# Digital_Connectors_and_IHM.net
KiCad netlist of a schematic drawn in Altium Designer
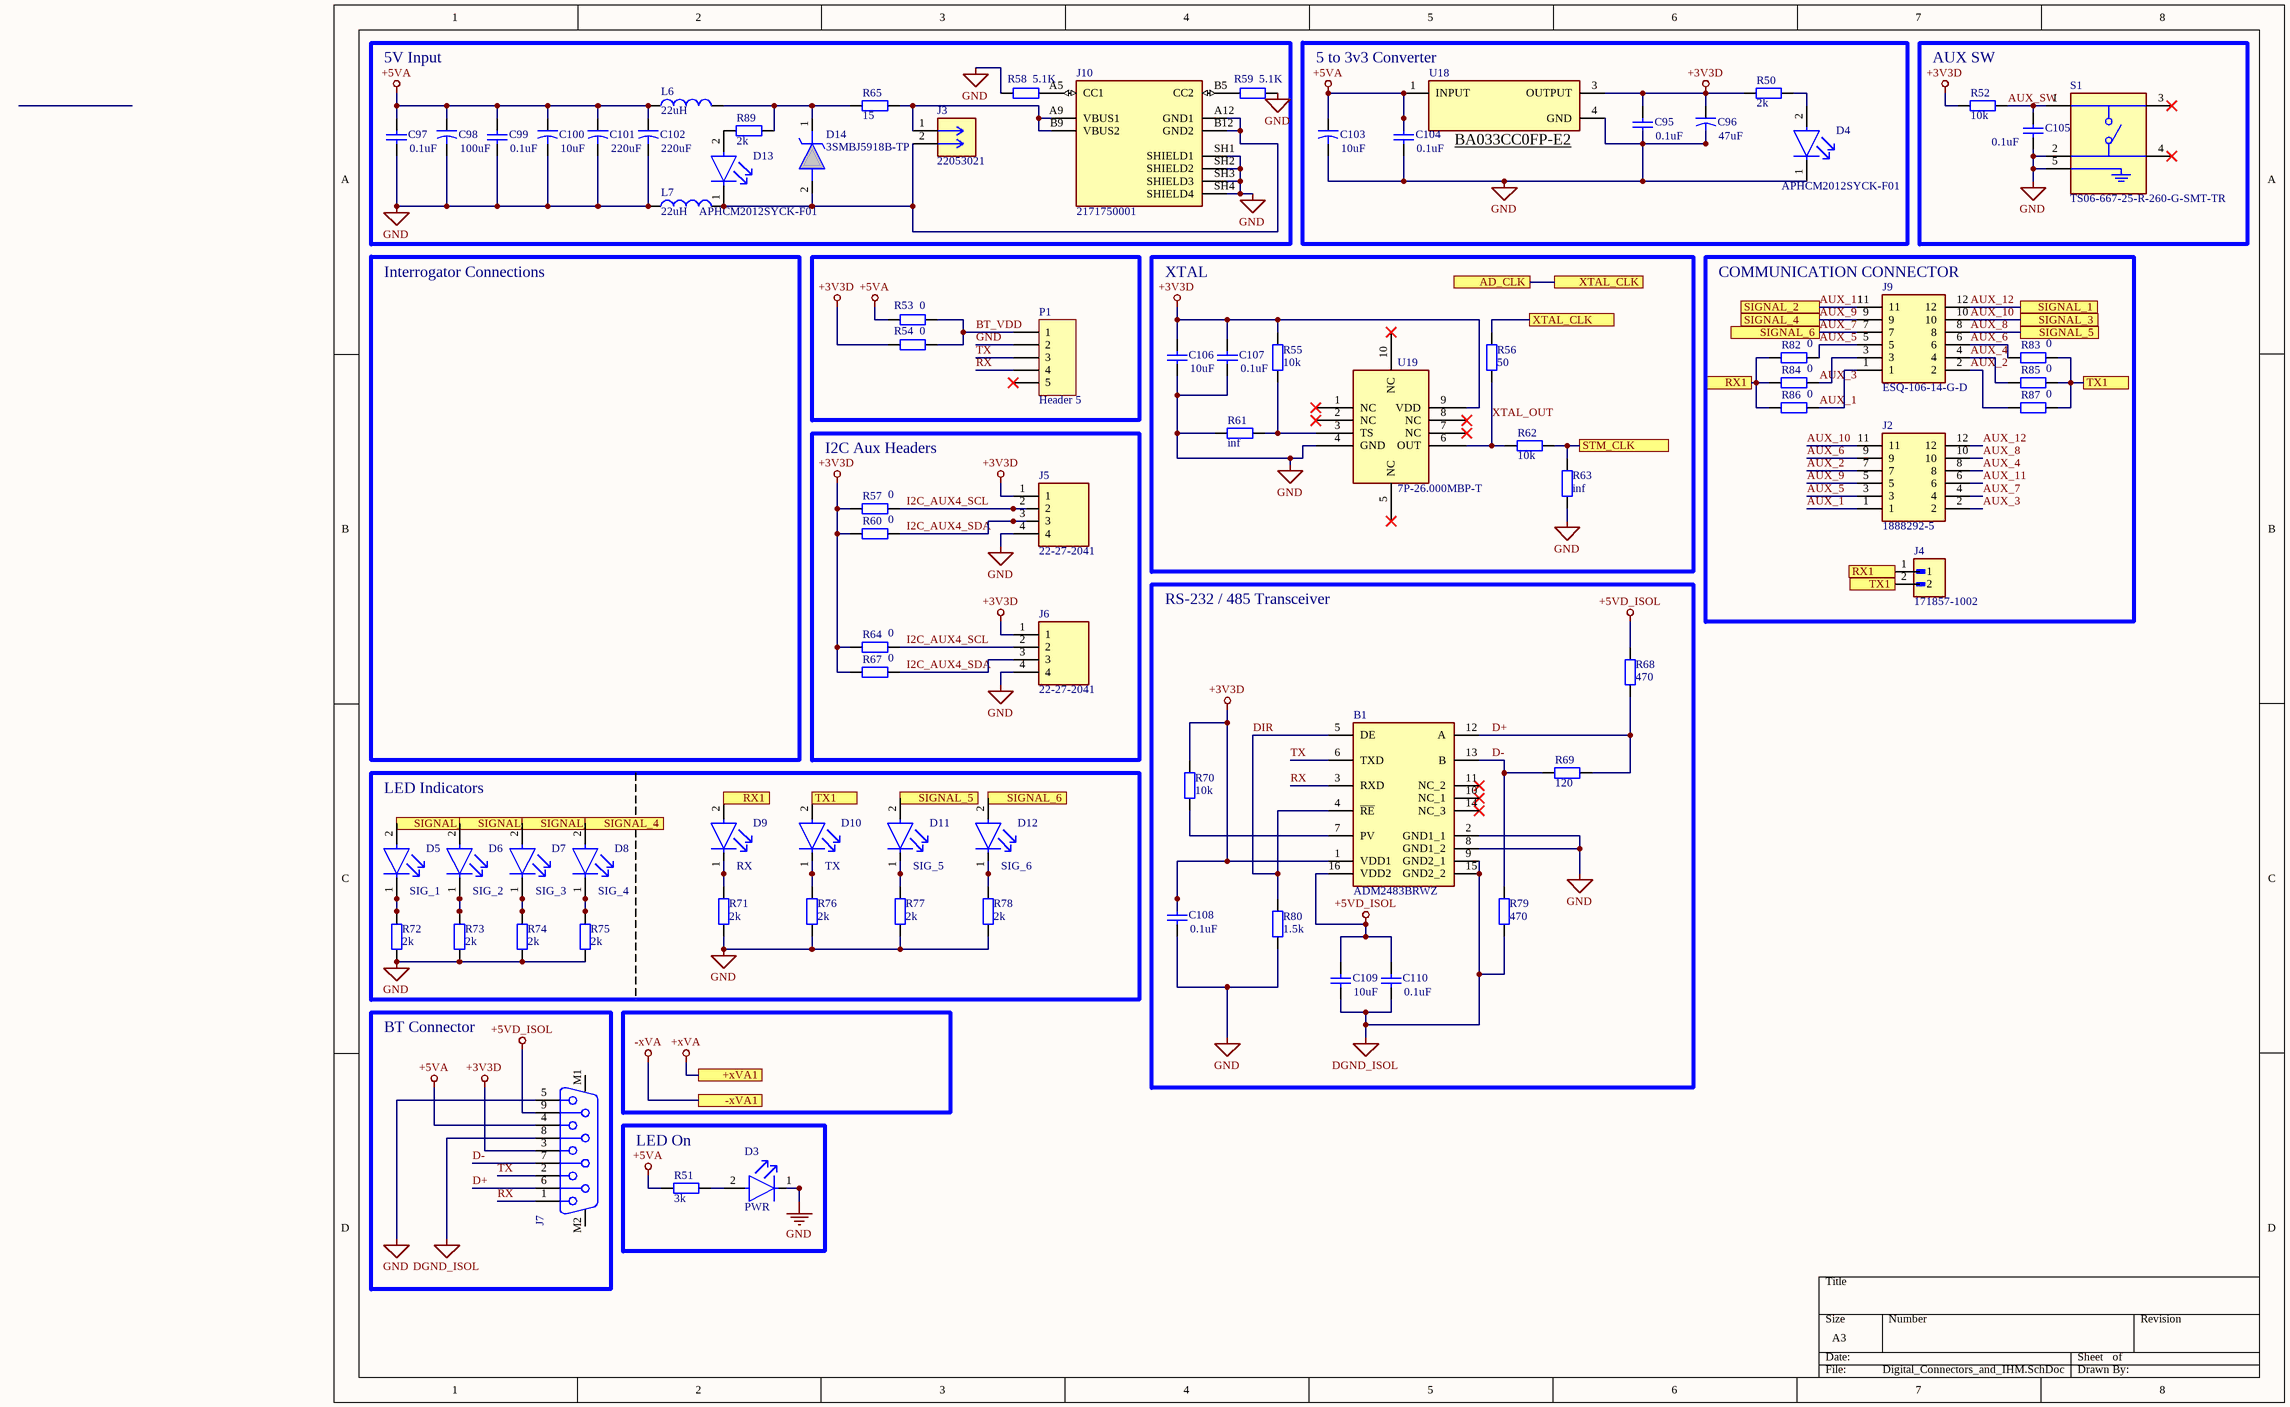
[diagram p0: Digital_Connectors_and_IHM.SchDoc]

(export (version "E")
  (design (tool "Eeschema 10.0.6"))
  (components
    (comp (ref "B1")
      (value "ADM2483BRWZ")
      (footprint "ADM2483BRWZ")
      (description "Half-Duplex, iCoupler Isolated RS-485 Transceiver")
      (fields (field (name "MOUSER PART NUMBER") "584-ADM2483BRWZ"))
      (libsource (lib "Lib_Schematic_Gyro_Single_Axis") (part "ADM2483BRWZ"))
    )
    (comp (ref "C95")
      (value "0.1uF")
      (footprint "CC_0805")
      (description "Capacitor")
      (fields (field (name "Comment") "Cap") (field (name "PUBLISHER") "Altium Limited"))
      (libsource (lib "Miscellaneous Devices") (part "Cap"))
    )
    (comp (ref "C96")
      (value "47uF")
      (footprint "CC_0805")
      (description "Capacitor")
      (fields (field (name "Comment") "Cap2") (field (name "PUBLISHER") "Altium Limited"))
      (libsource (lib "Miscellaneous Devices") (part "Cap2"))
    )
    (comp (ref "C97")
      (value "0.1uF")
      (footprint "CC_0805")
      (description "Capacitor")
      (fields (field (name "Comment") "Cap") (field (name "PUBLISHER") "Altium Limited"))
      (libsource (lib "Miscellaneous Devices") (part "Cap"))
    )
    (comp (ref "C98")
      (value "100uF")
      (footprint "CC_0805")
      (description "Capacitor")
      (fields (field (name "Comment") "Cap2") (field (name "PUBLISHER") "Altium Limited"))
      (libsource (lib "Miscellaneous Devices") (part "Cap2"))
    )
    (comp (ref "C99")
      (value "0.1uF")
      (footprint "CC_0805")
      (description "Capacitor")
      (fields (field (name "Comment") "Cap") (field (name "PUBLISHER") "Altium Limited"))
      (libsource (lib "Miscellaneous Devices") (part "Cap"))
    )
    (comp (ref "C100")
      (value "10uF")
      (footprint "CC_0805")
      (description "Capacitor")
      (fields (field (name "Comment") "Cap2") (field (name "PUBLISHER") "Altium Limited"))
      (libsource (lib "Miscellaneous Devices") (part "Cap2"))
    )
    (comp (ref "C101")
      (value "220uF")
      (footprint "CC_0805")
      (description "Capacitor")
      (fields (field (name "Comment") "Cap2") (field (name "PUBLISHER") "Altium Limited"))
      (libsource (lib "Miscellaneous Devices") (part "Cap2"))
    )
    (comp (ref "C102")
      (value "220uF")
      (footprint "CC_0805")
      (description "Capacitor")
      (fields (field (name "Comment") "Cap2") (field (name "PUBLISHER") "Altium Limited"))
      (libsource (lib "Miscellaneous Devices") (part "Cap2"))
    )
    (comp (ref "C103")
      (value "10uF")
      (footprint "CC_0805")
      (description "Capacitor")
      (fields (field (name "Comment") "Cap2") (field (name "PUBLISHER") "Altium Limited"))
      (libsource (lib "Miscellaneous Devices") (part "Cap2"))
    )
    (comp (ref "C104")
      (value "0.1uF")
      (footprint "CC_0805")
      (description "Capacitor")
      (fields (field (name "Comment") "Cap") (field (name "PUBLISHER") "Altium Limited"))
      (libsource (lib "Miscellaneous Devices") (part "Cap"))
    )
    (comp (ref "C105")
      (value "0.1uF")
      (footprint "CC_0805")
      (description "Capacitor")
      (fields (field (name "Comment") "Cap") (field (name "PUBLISHER") "Altium Limited"))
      (libsource (lib "Miscellaneous Devices") (part "Cap"))
    )
    (comp (ref "C106")
      (value "10uF")
      (footprint "CC_0805")
      (description "Capacitor")
      (fields (field (name "Comment") "Cap") (field (name "PUBLISHER") "Altium Limited"))
      (libsource (lib "Miscellaneous Devices") (part "Cap"))
    )
    (comp (ref "C107")
      (value "0.1uF")
      (footprint "CC_0805")
      (description "Capacitor")
      (fields (field (name "Comment") "Cap") (field (name "PUBLISHER") "Altium Limited"))
      (libsource (lib "Miscellaneous Devices") (part "Cap"))
    )
    (comp (ref "C108")
      (value "0.1uF")
      (footprint "CC_0805")
      (description "Capacitor")
      (fields (field (name "Comment") "Cap") (field (name "PUBLISHER") "Altium Limited"))
      (libsource (lib "Miscellaneous Devices") (part "Cap"))
    )
    (comp (ref "C109")
      (value "10uF")
      (footprint "CC_0805")
      (description "Capacitor")
      (fields (field (name "Comment") "Cap") (field (name "PUBLISHER") "Altium Limited"))
      (libsource (lib "Miscellaneous Devices") (part "Cap"))
    )
    (comp (ref "C110")
      (value "0.1uF")
      (footprint "CC_0805")
      (description "Capacitor")
      (fields (field (name "Comment") "Cap") (field (name "PUBLISHER") "Altium Limited"))
      (libsource (lib "Miscellaneous Devices") (part "Cap"))
    )
    (comp (ref "D3")
      (value "PWR")
      (footprint "FP-APHCM2012SYCK-F01-MFG")
      (description "LED YELLOW CLEAR CHIP SMD")
      (libsource (lib "Altium Content Vault") (part "8706943c75ba83719d021d2fdc84c58"))
    )
    (comp (ref "D4")
      (value "APHCM2012SYCK-F01")
      (footprint "FP-APHCM2012SYCK-F01-MFG")
      (description "LED YELLOW CLEAR CHIP SMD")
      (libsource (lib "Altium Content Vault") (part "8706943c75ba83719d021d2fdc84c58"))
    )
    (comp (ref "D5")
      (value "SIG_1")
      (footprint "FP-APHCM2012SYCK-F01-MFG")
      (description "LED YELLOW CLEAR CHIP SMD")
      (libsource (lib "Altium Content Vault") (part "8706943c75ba83719d021d2fdc84c58"))
    )
    (comp (ref "D6")
      (value "SIG_2")
      (footprint "FP-APHCM2012SYCK-F01-MFG")
      (description "LED YELLOW CLEAR CHIP SMD")
      (libsource (lib "Altium Content Vault") (part "8706943c75ba83719d021d2fdc84c58"))
    )
    (comp (ref "D7")
      (value "SIG_3")
      (footprint "FP-APHCM2012SYCK-F01-MFG")
      (description "LED YELLOW CLEAR CHIP SMD")
      (libsource (lib "Altium Content Vault") (part "8706943c75ba83719d021d2fdc84c58"))
    )
    (comp (ref "D8")
      (value "SIG_4")
      (footprint "FP-APHCM2012SYCK-F01-MFG")
      (description "LED YELLOW CLEAR CHIP SMD")
      (libsource (lib "Altium Content Vault") (part "8706943c75ba83719d021d2fdc84c58"))
    )
    (comp (ref "D9")
      (value "RX")
      (footprint "FP-APHCM2012SYCK-F01-MFG")
      (description "LED YELLOW CLEAR CHIP SMD")
      (libsource (lib "Altium Content Vault") (part "8706943c75ba83719d021d2fdc84c58"))
    )
    (comp (ref "D10")
      (value "TX")
      (footprint "FP-APHCM2012SYCK-F01-MFG")
      (description "LED YELLOW CLEAR CHIP SMD")
      (libsource (lib "Altium Content Vault") (part "8706943c75ba83719d021d2fdc84c58"))
    )
    (comp (ref "D11")
      (value "SIG_5")
      (footprint "FP-APHCM2012SYCK-F01-MFG")
      (description "LED YELLOW CLEAR CHIP SMD")
      (libsource (lib "Altium Content Vault") (part "8706943c75ba83719d021d2fdc84c58"))
    )
    (comp (ref "D12")
      (value "SIG_6")
      (footprint "FP-APHCM2012SYCK-F01-MFG")
      (description "LED YELLOW CLEAR CHIP SMD")
      (libsource (lib "Altium Content Vault") (part "8706943c75ba83719d021d2fdc84c58"))
    )
    (comp (ref "D13")
      (value "APHCM2012SYCK-F01")
      (footprint "FP-APHCM2012SYCK-F01-MFG")
      (description "LED YELLOW CLEAR CHIP SMD")
      (libsource (lib "Altium Content Vault") (part "8706943c75ba83719d021d2fdc84c58"))
    )
    (comp (ref "D14")
      (value "3SMBJ5918B-TP")
      (footprint "3SMBJ5918B-TP")
      (description "Zener Diodes")
      (fields (field (name "MOUSER PART NUMBER") "833-3SMBJ5918B-TP"))
      (libsource (lib "Lib_Schematic_IFOG_Interrogator") (part "3SMBJ5918B-TP"))
    )
    (comp (ref "J2")
      (value "1888292-5")
      (footprint "TE_1888292-5")
      (description "12 Position, Elevated Socket Strip, 0.100&quot; Pitch")
      (fields
        (field (name "MANUFACTURER_PART_NUMBER") "ESQ-106-14-G-D")
        (field (name "MOUSER PART NUMBER") "200-ESQ10614GD")
      )
      (libsource (lib "Lib_Schematic_IFOG_Interrogator") (part "1888292-5"))
    )
    (comp (ref "J3")
      (value "22053021")
      (footprint "22-05-3021")
      (libsource (lib "Lib_Schematic_Gyro_Single_Axis") (part "22053021"))
    )
    (comp (ref "J4")
      (value "171857-1002")
      (footprint "MOLEX_171857-1002")
      (fields (field (name "MF") "{'manufacturer': u'Molex'}"))
      (libsource (lib "Lib_Schematic_IFOG_Interrogator") (part "171857-1002"))
    )
    (comp (ref "J5")
      (value "22-27-2041")
      (footprint "22-27-2041")
      (description "Headers & Wire Housings 4 POS HEADER")
      (fields (field (name "MOUSER PART NUMBER") "538-22-27-2041"))
      (libsource (lib "Lib_Schematic_Gyro_Single_Axis") (part "22-27-2041"))
    )
    (comp (ref "J6")
      (value "22-27-2041")
      (footprint "22-27-2041")
      (description "Headers & Wire Housings 4 POS HEADER")
      (fields (field (name "MOUSER PART NUMBER") "538-22-27-2041"))
      (libsource (lib "Lib_Schematic_Gyro_Single_Axis") (part "22-27-2041"))
    )
    (comp (ref "J7")
      (value "618009231121")
      (footprint "618009231121")
      (description "WR-DSUB 8.08mm Female PCB Connector with Hex Screw, THT, Angled, 9p")
      (fields (field (name "MANUFACTURER") "Wurth Elektronik"))
      (libsource (lib "Lib_Schematic_Gyro_Single_Axis") (part "618009231121"))
    )
    (comp (ref "J9")
      (value "ESQ-106-14-G-D")
      (footprint "ESQ-106-Y-X-D")
      (description "12 Position, Elevated Socket Strip, 0.100&quot; Pitch")
      (fields (field (name "MOUSER PART NUMBER") "200-ESQ10614GD"))
      (libsource (lib "Lib_Schematic_IFOG_Interrogator") (part "ESQ-106-14-G-D"))
    )
    (comp (ref "J10")
      (value "2171750001")
      (footprint "MOLEX_2171750001")
      (fields (field (name "MF") "Molex"))
      (libsource (lib "Lib_Schematic_IFOG_Interrogator") (part "2171750001"))
    )
    (comp (ref "L6")
      (value "22uH")
      (footprint "WE-PMI_0805_H0.5")
      (description "Inductor")
      (fields (field (name "PUBLISHER") "Altium Limited"))
      (libsource (lib "Miscellaneous Devices") (part "Inductor"))
    )
    (comp (ref "L7")
      (value "22uH")
      (footprint "WE-PMI_0805_H0.5")
      (description "Inductor")
      (fields (field (name "PUBLISHER") "Altium Limited"))
      (libsource (lib "Miscellaneous Devices") (part "Inductor"))
    )
    (comp (ref "P1")
      (value "Header 5")
      (footprint "HDR1X5")
      (description "Header, 5-Pin")
      (fields (field (name "PUBLISHER") "Altium Limited"))
      (libsource (lib "Miscellaneous Connectors") (part "Header 5"))
    )
    (comp (ref "R50")
      (value "2k")
      (footprint "RR_1220")
      (description "Resistor")
      (fields (field (name "Comment") "Res2") (field (name "PUBLISHER") "Altium Limited"))
      (libsource (lib "") (part "Res2_2"))
    )
    (comp (ref "R51")
      (value "3k")
      (footprint "RR_1220")
      (description "Resistor")
      (fields (field (name "Comment") "Res2") (field (name "PUBLISHER") "Altium Limited"))
      (libsource (lib "Miscellaneous Devices") (part "Res2"))
    )
    (comp (ref "R52")
      (value "10k")
      (footprint "RR_1220")
      (description "Resistor")
      (fields (field (name "Comment") "Res2") (field (name "PUBLISHER") "Altium Limited"))
      (libsource (lib "") (part "Res2_2"))
    )
    (comp (ref "R53")
      (value "0")
      (footprint "RR_1220")
      (description "Resistor")
      (fields (field (name "Comment") "Res2") (field (name "PUBLISHER") "Altium Limited"))
      (libsource (lib "") (part "Res2_2"))
    )
    (comp (ref "R54")
      (value "0")
      (footprint "RR_1220")
      (description "Resistor")
      (fields (field (name "Comment") "Res2") (field (name "PUBLISHER") "Altium Limited"))
      (libsource (lib "") (part "Res2_2"))
    )
    (comp (ref "R55")
      (value "10k")
      (footprint "RR_1220")
      (description "Resistor")
      (fields (field (name "Comment") "Res2") (field (name "PUBLISHER") "Altium Limited"))
      (libsource (lib "") (part "Res2_3"))
    )
    (comp (ref "R56")
      (value "50")
      (footprint "RR_1220")
      (description "Resistor")
      (fields (field (name "Comment") "Res2") (field (name "PUBLISHER") "Altium Limited"))
      (libsource (lib "") (part "Res2_3"))
    )
    (comp (ref "R57")
      (value "0")
      (footprint "RR_1220")
      (description "Resistor")
      (fields (field (name "Comment") "Res2") (field (name "PUBLISHER") "Altium Limited"))
      (libsource (lib "") (part "Res2_2"))
    )
    (comp (ref "R58")
      (value "5.1K")
      (footprint "RR_1220")
      (description "Resistor")
      (fields (field (name "Comment") "Res2") (field (name "PUBLISHER") "Altium Limited"))
      (libsource (lib "") (part "Res2_2"))
    )
    (comp (ref "R59")
      (value "5.1K")
      (footprint "RR_1220")
      (description "Resistor")
      (fields (field (name "Comment") "Res2") (field (name "PUBLISHER") "Altium Limited"))
      (libsource (lib "") (part "Res2_2"))
    )
    (comp (ref "R60")
      (value "0")
      (footprint "RR_1220")
      (description "Resistor")
      (fields (field (name "Comment") "Res2") (field (name "PUBLISHER") "Altium Limited"))
      (libsource (lib "") (part "Res2_2"))
    )
    (comp (ref "R61")
      (value "inf")
      (footprint "RR_1220")
      (description "Resistor")
      (fields (field (name "Comment") "Res2") (field (name "PUBLISHER") "Altium Limited"))
      (libsource (lib "") (part "Res2_2"))
    )
    (comp (ref "R62")
      (value "10k")
      (footprint "RR_1220")
      (description "Resistor")
      (fields (field (name "Comment") "Res2") (field (name "PUBLISHER") "Altium Limited"))
      (libsource (lib "Miscellaneous Devices") (part "Res2"))
    )
    (comp (ref "R63")
      (value "inf")
      (footprint "RR_1220")
      (description "Resistor")
      (fields (field (name "Comment") "Res2") (field (name "PUBLISHER") "Altium Limited"))
      (libsource (lib "") (part "Res2_1"))
    )
    (comp (ref "R64")
      (value "0")
      (footprint "RR_1220")
      (description "Resistor")
      (fields (field (name "Comment") "Res2") (field (name "PUBLISHER") "Altium Limited"))
      (libsource (lib "") (part "Res2_2"))
    )
    (comp (ref "R65")
      (value "15")
      (footprint "RR_1220")
      (description "Resistor")
      (fields (field (name "Comment") "Res2") (field (name "PUBLISHER") "Altium Limited"))
      (libsource (lib "Miscellaneous Devices") (part "Res2"))
    )
    (comp (ref "R67")
      (value "0")
      (footprint "RR_1220")
      (description "Resistor")
      (fields (field (name "Comment") "Res2") (field (name "PUBLISHER") "Altium Limited"))
      (libsource (lib "") (part "Res2_2"))
    )
    (comp (ref "R68")
      (value "470")
      (footprint "RR_1220")
      (description "Resistor")
      (fields (field (name "Comment") "Res2") (field (name "PUBLISHER") "Altium Limited"))
      (libsource (lib "") (part "Res2_1"))
    )
    (comp (ref "R69")
      (value "120")
      (footprint "RR_1220")
      (description "Resistor")
      (fields (field (name "Comment") "Res2") (field (name "PUBLISHER") "Altium Limited"))
      (libsource (lib "Miscellaneous Devices") (part "Res2"))
    )
    (comp (ref "R70")
      (value "10k")
      (footprint "RR_1220")
      (description "Resistor")
      (fields (field (name "Comment") "Res2") (field (name "PUBLISHER") "Altium Limited"))
      (libsource (lib "") (part "Res2_1"))
    )
    (comp (ref "R71")
      (value "2k")
      (footprint "RR_1220")
      (description "Resistor")
      (fields (field (name "Comment") "Res2") (field (name "PUBLISHER") "Altium Limited"))
      (libsource (lib "") (part "Res2_1"))
    )
    (comp (ref "R72")
      (value "2k")
      (footprint "RR_1220")
      (description "Resistor")
      (fields (field (name "Comment") "Res2") (field (name "PUBLISHER") "Altium Limited"))
      (libsource (lib "") (part "Res2_3"))
    )
    (comp (ref "R73")
      (value "2k")
      (footprint "RR_1220")
      (description "Resistor")
      (fields (field (name "Comment") "Res2") (field (name "PUBLISHER") "Altium Limited"))
      (libsource (lib "") (part "Res2_3"))
    )
    (comp (ref "R74")
      (value "2k")
      (footprint "RR_1220")
      (description "Resistor")
      (fields (field (name "Comment") "Res2") (field (name "PUBLISHER") "Altium Limited"))
      (libsource (lib "") (part "Res2_3"))
    )
    (comp (ref "R75")
      (value "2k")
      (footprint "RR_1220")
      (description "Resistor")
      (fields (field (name "Comment") "Res2") (field (name "PUBLISHER") "Altium Limited"))
      (libsource (lib "") (part "Res2_3"))
    )
    (comp (ref "R76")
      (value "2k")
      (footprint "RR_1220")
      (description "Resistor")
      (fields (field (name "Comment") "Res2") (field (name "PUBLISHER") "Altium Limited"))
      (libsource (lib "") (part "Res2_1"))
    )
    (comp (ref "R77")
      (value "2k")
      (footprint "RR_1220")
      (description "Resistor")
      (fields (field (name "Comment") "Res2") (field (name "PUBLISHER") "Altium Limited"))
      (libsource (lib "") (part "Res2_3"))
    )
    (comp (ref "R78")
      (value "2k")
      (footprint "RR_1220")
      (description "Resistor")
      (fields (field (name "Comment") "Res2") (field (name "PUBLISHER") "Altium Limited"))
      (libsource (lib "") (part "Res2_3"))
    )
    (comp (ref "R79")
      (value "470")
      (footprint "RR_1220")
      (description "Resistor")
      (fields (field (name "Comment") "Res2") (field (name "PUBLISHER") "Altium Limited"))
      (libsource (lib "") (part "Res2_1"))
    )
    (comp (ref "R80")
      (value "1.5k")
      (footprint "RR_1220")
      (description "Resistor")
      (fields (field (name "Comment") "Res2") (field (name "PUBLISHER") "Altium Limited"))
      (libsource (lib "") (part "Res2_1"))
    )
    (comp (ref "R82")
      (value "0")
      (footprint "RR_1220")
      (description "Resistor")
      (fields (field (name "Comment") "Res2") (field (name "PUBLISHER") "Altium Limited"))
      (libsource (lib "") (part "Res2_2"))
    )
    (comp (ref "R83")
      (value "0")
      (footprint "RR_1220")
      (description "Resistor")
      (fields (field (name "Comment") "Res2") (field (name "PUBLISHER") "Altium Limited"))
      (libsource (lib "") (part "Res2_2"))
    )
    (comp (ref "R84")
      (value "0")
      (footprint "RR_1220")
      (description "Resistor")
      (fields (field (name "Comment") "Res2") (field (name "PUBLISHER") "Altium Limited"))
      (libsource (lib "") (part "Res2_2"))
    )
    (comp (ref "R85")
      (value "0")
      (footprint "RR_1220")
      (description "Resistor")
      (fields (field (name "Comment") "Res2") (field (name "PUBLISHER") "Altium Limited"))
      (libsource (lib "") (part "Res2_2"))
    )
    (comp (ref "R86")
      (value "0")
      (footprint "RR_1220")
      (description "Resistor")
      (fields (field (name "Comment") "Res2") (field (name "PUBLISHER") "Altium Limited"))
      (libsource (lib "") (part "Res2_2"))
    )
    (comp (ref "R87")
      (value "0")
      (footprint "RR_1220")
      (description "Resistor")
      (fields (field (name "Comment") "Res2") (field (name "PUBLISHER") "Altium Limited"))
      (libsource (lib "") (part "Res2_2"))
    )
    (comp (ref "R89")
      (value "2k")
      (footprint "RR_1220")
      (description "Resistor")
      (fields (field (name "Comment") "Res2") (field (name "PUBLISHER") "Altium Limited"))
      (libsource (lib "Miscellaneous Devices") (part "Res2"))
    )
    (comp (ref "S1")
      (value "TS06-667-25-R-260-G-SMT-TR")
      (footprint "TS06-667-25-R-260-G-SMT-TR")
      (description "6 x 6.7 mm, 2.5 mm Actuator Height, 260 gf, Red, Surface Mount, SPST, Tactile Switch")
      (fields (field (name "MF") "Same Sky"))
      (libsource (lib "Lib_Schematic_Gyro_Single_Axis") (part "TS06-667-25-R-260-G-SMT-TR"))
    )
    (comp (ref "U18")
      (value "TLV2217-33KVURG3")
      (footprint "FP-KVU0003A-MFG")
      (description "IC REG LINEAR 3.3V 500MA TO252-3")
      (libsource (lib "Altium Content Vault") (part "d5a15bcdf6b664122197b732e21c3ca"))
    )
    (comp (ref "U19")
      (value "7P-26.000MBP-T")
      (footprint "7P26000MBPT")
      (libsource (lib "Lib_Schematic_Gyro_Single_Axis") (part "7P-26.000MBP-T"))
    )
  )
  (nets
    (net (code "1") (name "+3V3D") (class "Default")
      (node (ref "B1") (pin "1") (pinfunction "VDD1_1") (pintype "passive"))
      (node (ref "C106") (pin "2") (pinfunction "2_2") (pintype "passive"))
      (node (ref "C107") (pin "2") (pinfunction "2_2") (pintype "passive"))
      (node (ref "C108") (pin "2") (pinfunction "2_2") (pintype "passive"))
      (node (ref "C95") (pin "2") (pinfunction "2_2") (pintype "passive"))
      (node (ref "C96") (pin "1") (pinfunction "1_1") (pintype "passive"))
      (node (ref "J5") (pin "1") (pinfunction "1_1") (pintype "passive"))
      (node (ref "J6") (pin "1") (pinfunction "1_1") (pintype "passive"))
      (node (ref "J7") (pin "3") (pinfunction "3_3") (pintype "passive"))
      (node (ref "R50") (pin "1") (pinfunction "1_1") (pintype "passive"))
      (node (ref "R52") (pin "1") (pinfunction "1_1") (pintype "passive"))
      (node (ref "R54") (pin "1") (pinfunction "1_1") (pintype "passive"))
      (node (ref "R55") (pin "2") (pinfunction "2_2") (pintype "passive"))
      (node (ref "R57") (pin "1") (pinfunction "1_1") (pintype "passive"))
      (node (ref "R60") (pin "1") (pinfunction "1_1") (pintype "passive"))
      (node (ref "R64") (pin "1") (pinfunction "1_1") (pintype "passive"))
      (node (ref "R67") (pin "1") (pinfunction "1_1") (pintype "passive"))
      (node (ref "R70") (pin "1") (pinfunction "1_1") (pintype "passive"))
      (node (ref "U18") (pin "3") (pinfunction "OUTPUT_3") (pintype "passive"))
      (node (ref "U19") (pin "9") (pinfunction "VDD_9") (pintype "passive"))
    )
    (net (code "2") (name "+5VA") (class "Default")
      (node (ref "C100") (pin "1") (pinfunction "1_1") (pintype "passive"))
      (node (ref "C101") (pin "1") (pinfunction "1_1") (pintype "passive"))
      (node (ref "C102") (pin "1") (pinfunction "1_1") (pintype "passive"))
      (node (ref "C103") (pin "1") (pinfunction "1_1") (pintype "passive"))
      (node (ref "C104") (pin "2") (pinfunction "2_2") (pintype "passive"))
      (node (ref "C97") (pin "2") (pinfunction "2_2") (pintype "passive"))
      (node (ref "C98") (pin "1") (pinfunction "1_1") (pintype "passive"))
      (node (ref "C99") (pin "2") (pinfunction "2_2") (pintype "passive"))
      (node (ref "J7") (pin "4") (pinfunction "4_4") (pintype "passive"))
      (node (ref "L6") (pin "1") (pinfunction "1_1") (pintype "passive"))
      (node (ref "R51") (pin "2") (pinfunction "2_2") (pintype "passive"))
      (node (ref "R53") (pin "1") (pinfunction "1_1") (pintype "passive"))
      (node (ref "U18") (pin "1") (pinfunction "INPUT_1") (pintype "passive"))
    )
    (net (code "3") (name "+5VD_ISOL") (class "Default")
      (node (ref "B1") (pin "16") (pinfunction "VDD2_16") (pintype "passive"))
      (node (ref "C109") (pin "2") (pinfunction "2_2") (pintype "passive"))
      (node (ref "C110") (pin "2") (pinfunction "2_2") (pintype "passive"))
      (node (ref "J7") (pin "9") (pinfunction "9_9") (pintype "passive"))
      (node (ref "R68") (pin "1") (pinfunction "1_1") (pintype "passive"))
    )
    (net (code "6") (name "/AD_CLK") (class "Default")
      (node (ref "R56") (pin "2") (pinfunction "2_2") (pintype "passive"))
    )
    (net (code "7") (name "/AUX_1") (class "Default")
      (node (ref "J2") (pin "1") (pinfunction "1_1") (pintype "passive"))
      (node (ref "J9") (pin "1") (pinfunction "1_1") (pintype "passive"))
      (node (ref "R86") (pin "2") (pinfunction "2_2") (pintype "passive"))
    )
    (net (code "8") (name "/AUX_2") (class "Default")
      (node (ref "J2") (pin "7") (pinfunction "7_7") (pintype "passive"))
      (node (ref "J9") (pin "2") (pinfunction "2_2") (pintype "passive"))
      (node (ref "R87") (pin "1") (pinfunction "1_1") (pintype "passive"))
    )
    (net (code "9") (name "/AUX_3") (class "Default")
      (node (ref "J2") (pin "2") (pinfunction "2_2") (pintype "passive"))
      (node (ref "J9") (pin "3") (pinfunction "3_3") (pintype "passive"))
      (node (ref "R84") (pin "2") (pinfunction "2_2") (pintype "passive"))
    )
    (net (code "10") (name "/AUX_4") (class "Default")
      (node (ref "J2") (pin "8") (pinfunction "8_8") (pintype "passive"))
      (node (ref "J9") (pin "4") (pinfunction "4_4") (pintype "passive"))
      (node (ref "R85") (pin "1") (pinfunction "1_1") (pintype "passive"))
    )
    (net (code "11") (name "/AUX_5") (class "Default")
      (node (ref "J2") (pin "3") (pinfunction "3_3") (pintype "passive"))
      (node (ref "J9") (pin "5") (pinfunction "5_5") (pintype "passive"))
      (node (ref "R82") (pin "2") (pinfunction "2_2") (pintype "passive"))
    )
    (net (code "12") (name "/AUX_6") (class "Default")
      (node (ref "J2") (pin "9") (pinfunction "9_9") (pintype "passive"))
      (node (ref "J9") (pin "6") (pinfunction "6_6") (pintype "passive"))
      (node (ref "R83") (pin "1") (pinfunction "1_1") (pintype "passive"))
    )
    (net (code "13") (name "/AUX_7") (class "Default")
      (node (ref "D12") (pin "2") (pinfunction "A_2") (pintype "passive"))
      (node (ref "J2") (pin "4") (pinfunction "4_4") (pintype "passive"))
      (node (ref "J9") (pin "7") (pinfunction "7_7") (pintype "passive"))
    )
    (net (code "14") (name "/AUX_8") (class "Default")
      (node (ref "D11") (pin "2") (pinfunction "A_2") (pintype "passive"))
      (node (ref "J2") (pin "10") (pinfunction "10_10") (pintype "passive"))
      (node (ref "J9") (pin "8") (pinfunction "8_8") (pintype "passive"))
    )
    (net (code "15") (name "/AUX_9") (class "Default")
      (node (ref "D8") (pin "2") (pinfunction "A_2") (pintype "passive"))
      (node (ref "J2") (pin "5") (pinfunction "5_5") (pintype "passive"))
      (node (ref "J9") (pin "9") (pinfunction "9_9") (pintype "passive"))
    )
    (net (code "16") (name "/AUX_10") (class "Default")
      (node (ref "D7") (pin "2") (pinfunction "A_2") (pintype "passive"))
      (node (ref "J2") (pin "11") (pinfunction "11_11") (pintype "passive"))
      (node (ref "J9") (pin "10") (pinfunction "10_10") (pintype "passive"))
    )
    (net (code "17") (name "/AUX_11") (class "Default")
      (node (ref "D6") (pin "2") (pinfunction "A_2") (pintype "passive"))
      (node (ref "J2") (pin "6") (pinfunction "6_6") (pintype "passive"))
      (node (ref "J9") (pin "11") (pinfunction "11_11") (pintype "passive"))
    )
    (net (code "18") (name "/AUX_12") (class "Default")
      (node (ref "D5") (pin "2") (pinfunction "A_2") (pintype "passive"))
      (node (ref "J2") (pin "12") (pinfunction "12_12") (pintype "passive"))
      (node (ref "J9") (pin "12") (pinfunction "12_12") (pintype "passive"))
    )
    (net (code "19") (name "/AUX_SW") (class "Default")
      (node (ref "C105") (pin "2") (pinfunction "2_2") (pintype "passive"))
      (node (ref "R52") (pin "2") (pinfunction "2_2") (pintype "passive"))
      (node (ref "S1") (pin "1") (pinfunction "1_1") (pintype "passive"))
    )
    (net (code "20") (name "/BT_VDD") (class "Default")
      (node (ref "P1") (pin "1") (pinfunction "1_1") (pintype "passive"))
      (node (ref "R53") (pin "2") (pinfunction "2_2") (pintype "passive"))
      (node (ref "R54") (pin "2") (pinfunction "2_2") (pintype "passive"))
    )
    (net (code "21") (name "/D+") (class "Default")
      (node (ref "B1") (pin "12") (pinfunction "A_12") (pintype "passive"))
      (node (ref "J7") (pin "6") (pinfunction "6_6") (pintype "passive"))
      (node (ref "R68") (pin "2") (pinfunction "2_2") (pintype "passive"))
      (node (ref "R69") (pin "1") (pinfunction "1_1") (pintype "passive"))
    )
    (net (code "22") (name "/D-") (class "Default")
      (node (ref "B1") (pin "13") (pinfunction "B_13") (pintype "passive"))
      (node (ref "J7") (pin "7") (pinfunction "7_7") (pintype "passive"))
      (node (ref "R69") (pin "2") (pinfunction "2_2") (pintype "passive"))
      (node (ref "R79") (pin "1") (pinfunction "1_1") (pintype "passive"))
    )
    (net (code "23") (name "/DIR") (class "Default")
      (node (ref "B1") (pin "4") (pinfunction "~{RE}_4") (pintype "passive"))
      (node (ref "B1") (pin "5") (pinfunction "DE_5") (pintype "passive"))
      (node (ref "R80") (pin "1") (pinfunction "1_1") (pintype "passive"))
    )
    (net (code "24") (name "/I2C_AUX4_SCL") (class "Default")
      (node (ref "J5") (pin "2") (pinfunction "2_2") (pintype "passive"))
      (node (ref "J6") (pin "2") (pinfunction "2_2") (pintype "passive"))
      (node (ref "R57") (pin "2") (pinfunction "2_2") (pintype "passive"))
      (node (ref "R64") (pin "2") (pinfunction "2_2") (pintype "passive"))
    )
    (net (code "25") (name "/I2C_AUX4_SDA") (class "Default")
      (node (ref "J5") (pin "3") (pinfunction "3_3") (pintype "passive"))
      (node (ref "J6") (pin "3") (pinfunction "3_3") (pintype "passive"))
      (node (ref "R60") (pin "2") (pinfunction "2_2") (pintype "passive"))
      (node (ref "R67") (pin "2") (pinfunction "2_2") (pintype "passive"))
    )
    (net (code "26") (name "/RX") (class "Default")
      (node (ref "B1") (pin "3") (pinfunction "RXD_3") (pintype "passive"))
      (node (ref "J7") (pin "1") (pinfunction "1_1") (pintype "passive"))
      (node (ref "P1") (pin "4") (pinfunction "4_4") (pintype "passive"))
    )
    (net (code "27") (name "/RX1") (class "Default")
      (node (ref "D9") (pin "2") (pinfunction "A_2") (pintype "passive"))
      (node (ref "J4") (pin "1") (pinfunction "1_1") (pintype "passive"))
      (node (ref "R82") (pin "1") (pinfunction "1_1") (pintype "passive"))
      (node (ref "R84") (pin "1") (pinfunction "1_1") (pintype "passive"))
      (node (ref "R86") (pin "1") (pinfunction "1_1") (pintype "passive"))
    )
    (net (code "28") (name "/STM_CLK") (class "Default")
      (node (ref "R62") (pin "1") (pinfunction "1_1") (pintype "passive"))
      (node (ref "R63") (pin "1") (pinfunction "1_1") (pintype "passive"))
    )
    (net (code "29") (name "/TX") (class "Default")
      (node (ref "B1") (pin "6") (pinfunction "TXD_6") (pintype "passive"))
      (node (ref "J7") (pin "2") (pinfunction "2_2") (pintype "passive"))
      (node (ref "P1") (pin "3") (pinfunction "3_3") (pintype "passive"))
    )
    (net (code "30") (name "/TX1") (class "Default")
      (node (ref "D10") (pin "2") (pinfunction "A_2") (pintype "passive"))
      (node (ref "J4") (pin "2") (pinfunction "2_2") (pintype "passive"))
      (node (ref "R83") (pin "2") (pinfunction "2_2") (pintype "passive"))
      (node (ref "R85") (pin "2") (pinfunction "2_2") (pintype "passive"))
      (node (ref "R87") (pin "2") (pinfunction "2_2") (pintype "passive"))
    )
    (net (code "31") (name "/XTAL_OUT") (class "Default")
      (node (ref "R56") (pin "1") (pinfunction "1_1") (pintype "passive"))
      (node (ref "R62") (pin "2") (pinfunction "2_2") (pintype "passive"))
      (node (ref "U19") (pin "6") (pinfunction "OUT_6") (pintype "passive"))
    )
    (net (code "32") (name "DGND_ISOL") (class "Default")
      (node (ref "B1") (pin "15") (pinfunction "GND2_2_15") (pintype "passive"))
      (node (ref "B1") (pin "9") (pinfunction "GND2_1_9") (pintype "passive"))
      (node (ref "C109") (pin "1") (pinfunction "1_1") (pintype "passive"))
      (node (ref "C110") (pin "1") (pinfunction "1_1") (pintype "passive"))
      (node (ref "J7") (pin "8") (pinfunction "8_8") (pintype "passive"))
      (node (ref "R79") (pin "2") (pinfunction "2_2") (pintype "passive"))
    )
    (net (code "33") (name "GND") (class "Default")
      (node (ref "B1") (pin "2") (pinfunction "GND1_1_2") (pintype "passive"))
      (node (ref "B1") (pin "8") (pinfunction "GND1_2_8") (pintype "passive"))
      (node (ref "C100") (pin "2") (pinfunction "2_2") (pintype "passive"))
      (node (ref "C101") (pin "2") (pinfunction "2_2") (pintype "passive"))
      (node (ref "C102") (pin "2") (pinfunction "2_2") (pintype "passive"))
      (node (ref "C103") (pin "2") (pinfunction "2_2") (pintype "passive"))
      (node (ref "C104") (pin "1") (pinfunction "1_1") (pintype "passive"))
      (node (ref "C105") (pin "1") (pinfunction "1_1") (pintype "passive"))
      (node (ref "C106") (pin "1") (pinfunction "1_1") (pintype "passive"))
      (node (ref "C107") (pin "1") (pinfunction "1_1") (pintype "passive"))
      (node (ref "C108") (pin "1") (pinfunction "1_1") (pintype "passive"))
      (node (ref "C95") (pin "1") (pinfunction "1_1") (pintype "passive"))
      (node (ref "C96") (pin "2") (pinfunction "2_2") (pintype "passive"))
      (node (ref "C97") (pin "1") (pinfunction "1_1") (pintype "passive"))
      (node (ref "C98") (pin "2") (pinfunction "2_2") (pintype "passive"))
      (node (ref "C99") (pin "1") (pinfunction "1_1") (pintype "passive"))
      (node (ref "D3") (pin "1") (pinfunction "C_1") (pintype "passive"))
      (node (ref "D4") (pin "1") (pinfunction "C_1") (pintype "passive"))
      (node (ref "J10") (pin "SH1") (pinfunction "SHIELD1_SH1") (pintype "passive"))
      (node (ref "J10") (pin "SH2") (pinfunction "SHIELD2_SH2") (pintype "passive"))
      (node (ref "J10") (pin "SH3") (pinfunction "SHIELD3_SH3") (pintype "passive"))
      (node (ref "J10") (pin "SH4") (pinfunction "SHIELD4_SH4") (pintype "passive"))
      (node (ref "J5") (pin "4") (pinfunction "4_4") (pintype "passive"))
      (node (ref "J6") (pin "4") (pinfunction "4_4") (pintype "passive"))
      (node (ref "J7") (pin "5") (pinfunction "5_5") (pintype "passive"))
      (node (ref "L7") (pin "1") (pinfunction "1_1") (pintype "passive"))
      (node (ref "P1") (pin "2") (pinfunction "2_2") (pintype "passive"))
      (node (ref "R58") (pin "1") (pinfunction "1_1") (pintype "passive"))
      (node (ref "R59") (pin "2") (pinfunction "2_2") (pintype "passive"))
      (node (ref "R61") (pin "1") (pinfunction "1_1") (pintype "passive"))
      (node (ref "R63") (pin "2") (pinfunction "2_2") (pintype "passive"))
      (node (ref "R71") (pin "2") (pinfunction "2_2") (pintype "passive"))
      (node (ref "R72") (pin "1") (pinfunction "1_1") (pintype "passive"))
      (node (ref "R73") (pin "1") (pinfunction "1_1") (pintype "passive"))
      (node (ref "R74") (pin "1") (pinfunction "1_1") (pintype "passive"))
      (node (ref "R75") (pin "1") (pinfunction "1_1") (pintype "passive"))
      (node (ref "R76") (pin "2") (pinfunction "2_2") (pintype "passive"))
      (node (ref "R77") (pin "1") (pinfunction "1_1") (pintype "passive"))
      (node (ref "R78") (pin "1") (pinfunction "1_1") (pintype "passive"))
      (node (ref "R80") (pin "2") (pinfunction "2_2") (pintype "passive"))
      (node (ref "S1") (pin "2") (pinfunction "2_2") (pintype "passive"))
      (node (ref "S1") (pin "5") (pinfunction "5_5") (pintype "passive"))
      (node (ref "U18") (pin "4") (pinfunction "GND_4") (pintype "power_in"))
      (node (ref "U19") (pin "4") (pinfunction "GND_4") (pintype "passive"))
    )
    (net (code "34") (name "Net-(B1-PV)") (class "Default")
      (node (ref "B1") (pin "7") (pinfunction "PV_7") (pintype "passive"))
      (node (ref "R70") (pin "2") (pinfunction "2_2") (pintype "passive"))
    )
    (net (code "35") (name "Net-(D3-A)") (class "Default")
      (node (ref "D3") (pin "2") (pinfunction "A_2") (pintype "passive"))
      (node (ref "R51") (pin "1") (pinfunction "1_1") (pintype "passive"))
    )
    (net (code "36") (name "Net-(D4-A)") (class "Default")
      (node (ref "D4") (pin "2") (pinfunction "A_2") (pintype "passive"))
      (node (ref "R50") (pin "2") (pinfunction "2_2") (pintype "passive"))
    )
    (net (code "37") (name "Net-(D5-C)") (class "Default")
      (node (ref "D5") (pin "1") (pinfunction "C_1") (pintype "passive"))
      (node (ref "R72") (pin "2") (pinfunction "2_2") (pintype "passive"))
    )
    (net (code "38") (name "Net-(D6-C)") (class "Default")
      (node (ref "D6") (pin "1") (pinfunction "C_1") (pintype "passive"))
      (node (ref "R73") (pin "2") (pinfunction "2_2") (pintype "passive"))
    )
    (net (code "39") (name "Net-(D7-C)") (class "Default")
      (node (ref "D7") (pin "1") (pinfunction "C_1") (pintype "passive"))
      (node (ref "R74") (pin "2") (pinfunction "2_2") (pintype "passive"))
    )
    (net (code "40") (name "Net-(D8-C)") (class "Default")
      (node (ref "D8") (pin "1") (pinfunction "C_1") (pintype "passive"))
      (node (ref "R75") (pin "2") (pinfunction "2_2") (pintype "passive"))
    )
    (net (code "41") (name "Net-(D9-C)") (class "Default")
      (node (ref "D9") (pin "1") (pinfunction "C_1") (pintype "passive"))
      (node (ref "R71") (pin "1") (pinfunction "1_1") (pintype "passive"))
    )
    (net (code "42") (name "Net-(D10-C)") (class "Default")
      (node (ref "D10") (pin "1") (pinfunction "C_1") (pintype "passive"))
      (node (ref "R76") (pin "1") (pinfunction "1_1") (pintype "passive"))
    )
    (net (code "43") (name "Net-(D11-C)") (class "Default")
      (node (ref "D11") (pin "1") (pinfunction "C_1") (pintype "passive"))
      (node (ref "R77") (pin "2") (pinfunction "2_2") (pintype "passive"))
    )
    (net (code "44") (name "Net-(D12-C)") (class "Default")
      (node (ref "D12") (pin "1") (pinfunction "C_1") (pintype "passive"))
      (node (ref "R78") (pin "2") (pinfunction "2_2") (pintype "passive"))
    )
    (net (code "45") (name "Net-(D13-A)") (class "Default")
      (node (ref "D13") (pin "2") (pinfunction "A_2") (pintype "passive"))
      (node (ref "R89") (pin "2") (pinfunction "2_2") (pintype "passive"))
    )
    (net (code "46") (name "Net-(D13-C)") (class "Default")
      (node (ref "D13") (pin "1") (pinfunction "C_1") (pintype "passive"))
      (node (ref "D14") (pin "2") (pinfunction "A_2") (pintype "passive"))
      (node (ref "J10") (pin "A12") (pinfunction "GND1_A12") (pintype "power_in"))
      (node (ref "J10") (pin "B12") (pinfunction "GND2_B12") (pintype "power_in"))
      (node (ref "J3") (pin "2") (pinfunction "2_2") (pintype "passive"))
      (node (ref "L7") (pin "2") (pinfunction "2_2") (pintype "passive"))
    )
    (net (code "47") (name "Net-(D14-K)") (class "Default")
      (node (ref "D14") (pin "1") (pinfunction "K_1") (pintype "passive"))
      (node (ref "L6") (pin "2") (pinfunction "2_2") (pintype "passive"))
      (node (ref "R65") (pin "2") (pinfunction "2_2") (pintype "passive"))
      (node (ref "R89") (pin "1") (pinfunction "1_1") (pintype "passive"))
    )
    (net (code "48") (name "Net-(J10-CC1)") (class "Default")
      (node (ref "J10") (pin "A5") (pinfunction "CC1_A5") (pintype "bidirectional"))
      (node (ref "R58") (pin "2") (pinfunction "2_2") (pintype "passive"))
    )
    (net (code "49") (name "Net-(J10-CC2)") (class "Default")
      (node (ref "J10") (pin "B5") (pinfunction "CC2_B5") (pintype "bidirectional"))
      (node (ref "R59") (pin "1") (pinfunction "1_1") (pintype "passive"))
    )
    (net (code "50") (name "Net-(J10-VBUS1)") (class "Default")
      (node (ref "J10") (pin "A9") (pinfunction "VBUS1_A9") (pintype "power_in"))
      (node (ref "J10") (pin "B9") (pinfunction "VBUS2_B9") (pintype "power_in"))
      (node (ref "J3") (pin "1") (pinfunction "1_1") (pintype "passive"))
      (node (ref "R65") (pin "1") (pinfunction "1_1") (pintype "passive"))
    )
    (net (code "51") (name "Net-(U19-TS)") (class "Default")
      (node (ref "R55") (pin "1") (pinfunction "1_1") (pintype "passive"))
      (node (ref "R61") (pin "2") (pinfunction "2_2") (pintype "passive"))
      (node (ref "U19") (pin "3") (pinfunction "TS_3") (pintype "passive"))
    )
    (net (code "52") (name "unconnected-(B1-NC_1-Pad10)") (class "Default")
      (node (ref "B1") (pin "10") (pinfunction "NC_1_10") (pintype "passive+no_connect"))
    )
    (net (code "53") (name "unconnected-(B1-NC_2-Pad11)") (class "Default")
      (node (ref "B1") (pin "11") (pinfunction "NC_2_11") (pintype "passive+no_connect"))
    )
    (net (code "54") (name "unconnected-(B1-NC_3-Pad14)") (class "Default")
      (node (ref "B1") (pin "14") (pinfunction "NC_3_14") (pintype "passive+no_connect"))
    )
    (net (code "55") (name "unconnected-(J7-PadM1)") (class "Default")
      (node (ref "J7") (pin "M1") (pinfunction "M1_M1") (pintype "passive"))
    )
    (net (code "56") (name "unconnected-(J7-PadM2)") (class "Default")
      (node (ref "J7") (pin "M2") (pinfunction "M2_M2") (pintype "passive"))
    )
    (net (code "57") (name "unconnected-(P1-Pad5)") (class "Default")
      (node (ref "P1") (pin "5") (pinfunction "5_5") (pintype "passive+no_connect"))
    )
    (net (code "58") (name "unconnected-(S1-Pad3)") (class "Default")
      (node (ref "S1") (pin "3") (pinfunction "3_3") (pintype "passive+no_connect"))
    )
    (net (code "59") (name "unconnected-(S1-Pad4)") (class "Default")
      (node (ref "S1") (pin "4") (pinfunction "4_4") (pintype "passive+no_connect"))
    )
    (net (code "60") (name "unconnected-(U19-NC-Pad1)") (class "Default")
      (node (ref "U19") (pin "1") (pinfunction "NC_1") (pintype "passive+no_connect"))
    )
    (net (code "61") (name "unconnected-(U19-NC-Pad2)") (class "Default")
      (node (ref "U19") (pin "2") (pinfunction "NC_2") (pintype "passive+no_connect"))
    )
    (net (code "62") (name "unconnected-(U19-NC-Pad5)") (class "Default")
      (node (ref "U19") (pin "5") (pinfunction "NC_5") (pintype "passive+no_connect"))
    )
    (net (code "63") (name "unconnected-(U19-NC-Pad7)") (class "Default")
      (node (ref "U19") (pin "7") (pinfunction "NC_7") (pintype "passive+no_connect"))
    )
    (net (code "64") (name "unconnected-(U19-NC-Pad8)") (class "Default")
      (node (ref "U19") (pin "8") (pinfunction "NC_8") (pintype "passive+no_connect"))
    )
    (net (code "65") (name "unconnected-(U19-NC-Pad10)") (class "Default")
      (node (ref "U19") (pin "10") (pinfunction "NC_10") (pintype "passive+no_connect"))
    )
  )
)
